# TSL2671.net
KiCad netlist of a schematic drawn in EAGLE
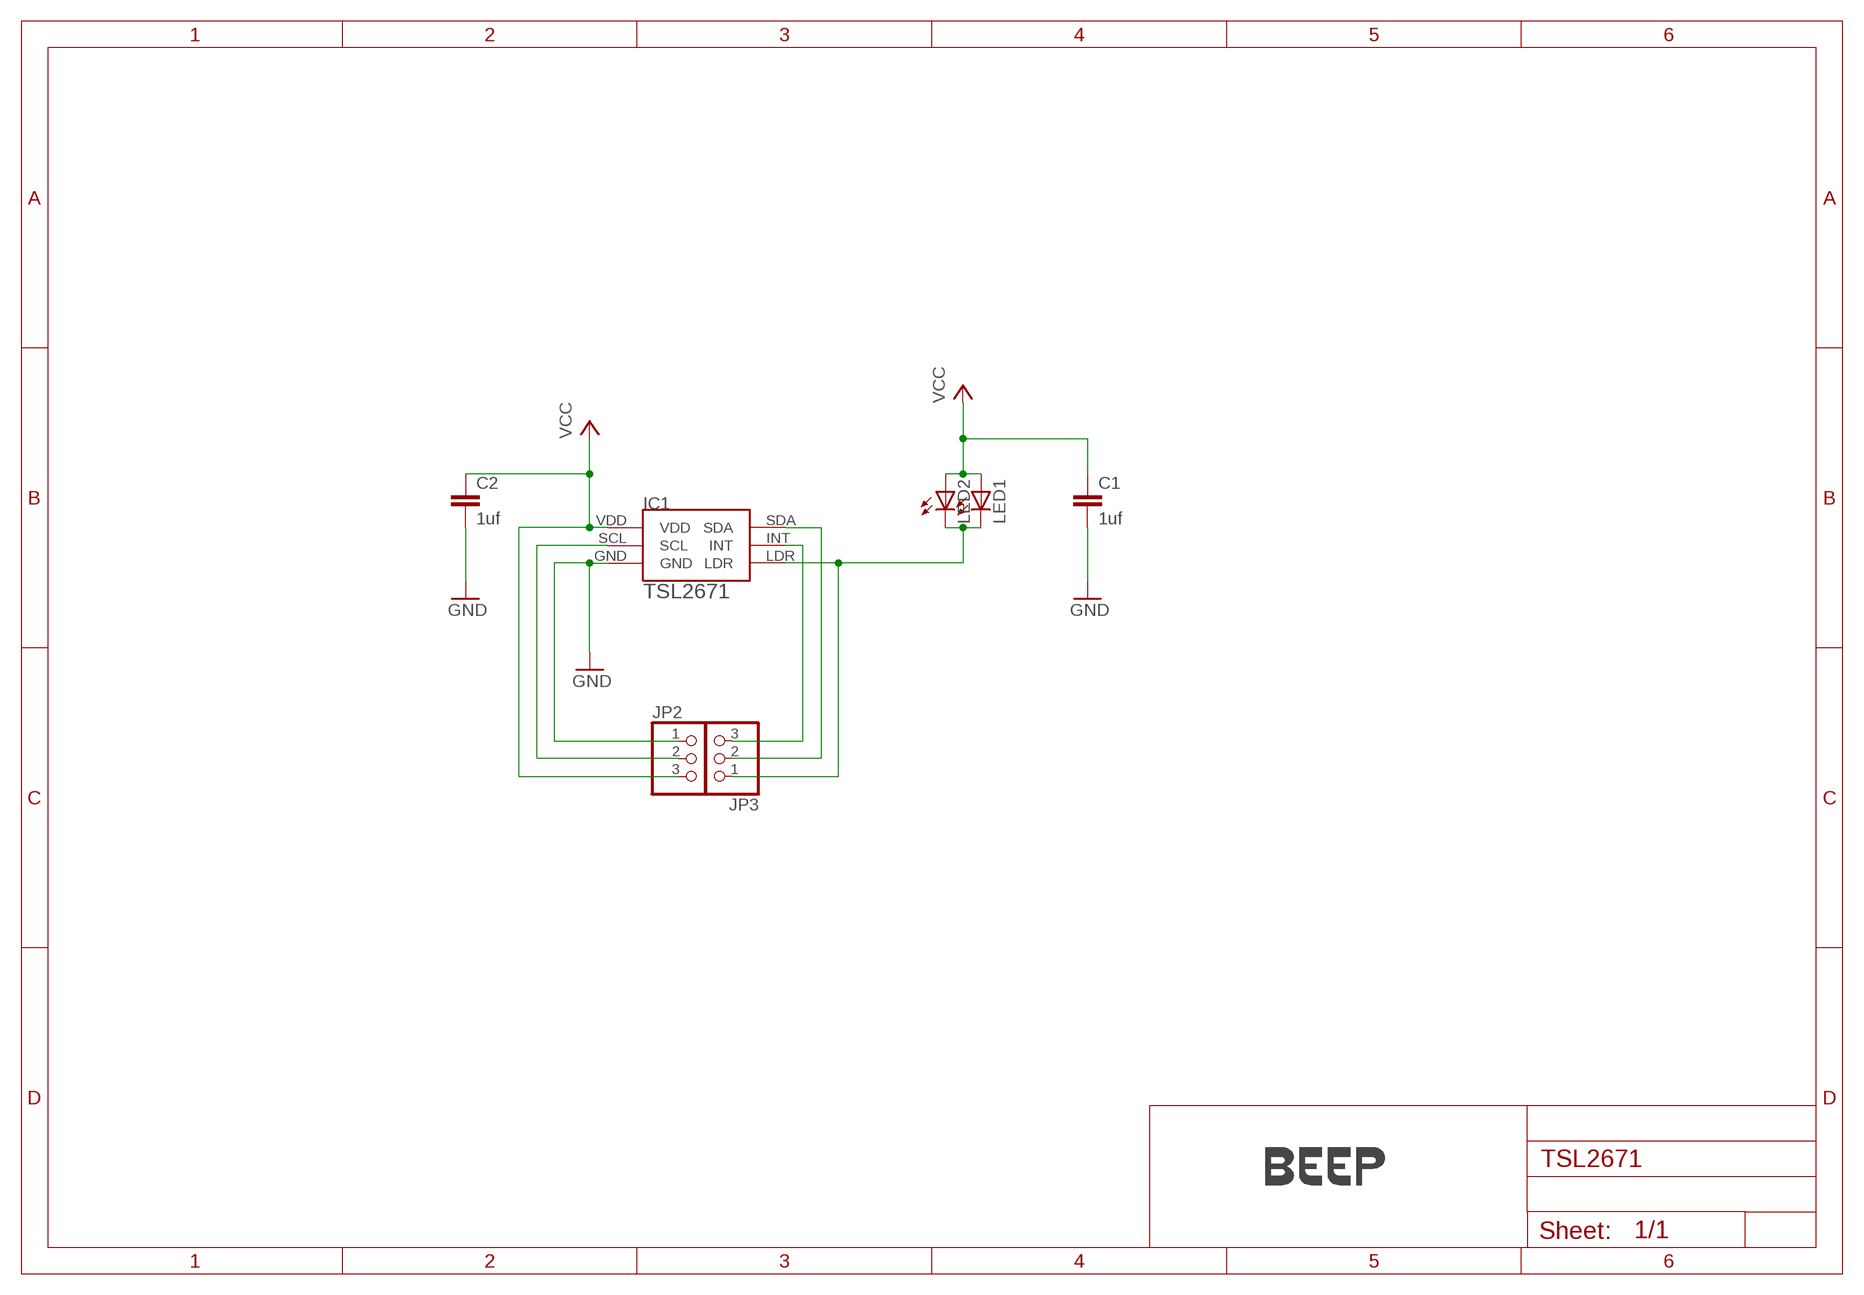
[diagram p0: schematic, sheet 1]

(export (version "E")
  (design (tool "Eeschema 10.0.6"))
  (components
    (comp (ref "C1")
      (value "1uf")
      (footprint "eagle-import:C025-025X050")
      (libsource (lib "eagle-import") (part "C-EU025-025X050"))
    )
    (comp (ref "C2")
      (value "1uf")
      (footprint "eagle-import:C0805K")
      (libsource (lib "eagle-import") (part "C-EUC0805K"))
    )
    (comp (ref "IC1")
      (value "TSL2671")
      (footprint "eagle-import:TSL2671")
      (libsource (lib "eagle-import") (part "TSL2671"))
    )
    (comp (ref "JP2")
      (value "PINHD-1X3")
      (footprint "eagle-import:1X03")
      (libsource (lib "eagle-import") (part "PINHD-1X3"))
    )
    (comp (ref "JP3")
      (value "PINHD-1X3")
      (footprint "eagle-import:1X03")
      (libsource (lib "eagle-import") (part "PINHD-1X3"))
    )
    (comp (ref "LED1")
      (value "LED5MM")
      (footprint "eagle-import:LED5MM")
      (libsource (lib "eagle-import") (part "LED5MM"))
    )
    (comp (ref "LED2")
      (value "LEDCHIP-LED0805")
      (footprint "eagle-import:CHIP-LED0805")
      (libsource (lib "eagle-import") (part "LEDCHIP-LED0805"))
    )
    (comp (ref "U$1")
      (value "LOGO-COPPER4")
      (footprint "eagle-import:COPPER4")
      (libsource (lib "eagle-import") (part "LOGO-COPPER4"))
    )
  )
  (nets
    (net (code "1") (name "GND") (class "Default")
      (node (ref "C1") (pin "2") (pinfunction "2_2") (pintype "passive"))
      (node (ref "C2") (pin "2") (pinfunction "2_2") (pintype "passive"))
      (node (ref "IC1") (pin "GND") (pinfunction "GND_GND") (pintype "power_in"))
      (node (ref "JP2") (pin "1") (pinfunction "1_1") (pintype "passive"))
    )
    (net (code "2") (name "Net-(IC1-PadINT)") (class "Default")
      (node (ref "IC1") (pin "INT") (pinfunction "INT_INT") (pintype "output"))
      (node (ref "JP3") (pin "3") (pinfunction "3_3") (pintype "passive"))
    )
    (net (code "3") (name "Net-(IC1-PadSCL)") (class "Default")
      (node (ref "IC1") (pin "SCL") (pinfunction "SCL_SCL") (pintype "bidirectional"))
      (node (ref "JP2") (pin "2") (pinfunction "2_2") (pintype "passive"))
    )
    (net (code "4") (name "Net-(IC1-PadSDA)") (class "Default")
      (node (ref "IC1") (pin "SDA") (pinfunction "SDA_SDA") (pintype "bidirectional"))
      (node (ref "JP3") (pin "2") (pinfunction "2_2") (pintype "passive"))
    )
    (net (code "5") (name "Net-(LED1-C)") (class "Default")
      (node (ref "IC1") (pin "LDR") (pinfunction "LDR_LDR") (pintype "power_in"))
      (node (ref "JP3") (pin "1") (pinfunction "1_1") (pintype "passive"))
      (node (ref "LED1") (pin "K") (pinfunction "C_K") (pintype "passive"))
      (node (ref "LED2") (pin "C") (pinfunction "C_C") (pintype "passive"))
    )
    (net (code "6") (name "VCC") (class "Default")
      (node (ref "C1") (pin "1") (pinfunction "1_1") (pintype "passive"))
      (node (ref "C2") (pin "1") (pinfunction "1_1") (pintype "passive"))
      (node (ref "IC1") (pin "VDD") (pinfunction "VDD_VDD") (pintype "power_in"))
      (node (ref "JP2") (pin "3") (pinfunction "3_3") (pintype "passive"))
      (node (ref "LED1") (pin "A") (pinfunction "A_A") (pintype "passive"))
      (node (ref "LED2") (pin "A") (pinfunction "A_A") (pintype "passive"))
    )
  )
)
